# GPS.net
KiCad netlist of a schematic drawn in Altium Designer
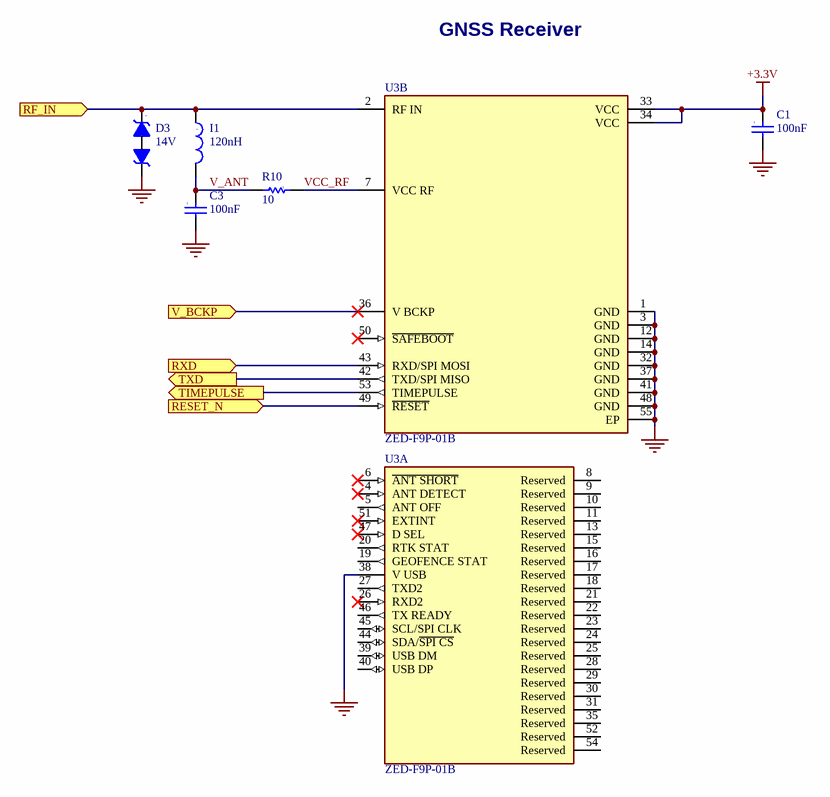
[diagram p0: GPS.SchDoc]

(export (version "E")
  (design (tool "Eeschema 10.0.6"))
  (components
    (comp (ref "C1")
      (value "100nF")
      (footprint "0402")
      (description "CAP CER .10UF 50V X7R 10% 0402")
      (fields
        (field (name "MANUFACTURER") "TDK Corporation")
        (field (name "MANUFACTURER PART NUMBER") "C1005X7R1H104K")
        (field (name "PUBLISHER") "Altium Limited")
      )
      (libsource (lib "General") (part "Cap"))
    )
    (comp (ref "C3")
      (value "100nF")
      (footprint "0402")
      (description "CAP CER .10UF 50V X7R 10% 0402")
      (fields
        (field (name "MANUFACTURER") "TDK Corporation")
        (field (name "MANUFACTURER PART NUMBER") "C1005X7R1H104K")
        (field (name "PUBLISHER") "Altium Limited")
      )
      (libsource (lib "General") (part "Cap"))
    )
    (comp (ref "D3")
      (value "Diode - Bidirectional Zener")
      (footprint "R0402")
      (description "LITTELFUSE - PESD0402-140 - DIODE, ESD PROTECTION, 0402, FULL REEL")
      (fields
        (field (name "MANUFACTURER") "Littelfuse")
        (field (name "MANUFACTURER PART NUMBER") "PESD0402-140")
        (field (name "WORKING VOLTAGE") "14V")
      )
      (libsource (lib "General") (part "Diode - Bidirectional Zener"))
    )
    (comp (ref "I1")
      (value "120nH")
      (footprint "0402")
      (description "Inductor RF Chip Wirewound 120nH 5% 100MHz 20Q-Factor 110mA 2.66Ohm DCR 0402 Paper T/R")
      (fields
        (field (name "MANUFACTURER") "Murata")
        (field (name "MANUFACTURER PART NUMBER") "LQW15ANR12J00D")
      )
      (libsource (lib "General") (part "Inductor"))
    )
    (comp (ref "R10")
      (value "10")
      (footprint "R0402")
      (description "RES SMD 10 OHM 5% 1/5W 0402")
      (fields
        (field (name "MANUFACTURER") "Rohm Semiconductor")
        (field (name "MANUFACTURER PART NUMBER") "ESR01MZPJ100")
      )
      (libsource (lib "General") (part "Res"))
    )
    (comp (ref "U3")
      (value "ZED-F9P-01B")
      (footprint "U-Blox_ZED-F9P")
      (fields (field (name "MANUFACTURER") "u-blox") (field (name "MANUFACTURER PART NUMBER") "ZED-F9P-01B"))
      (libsource (lib "Wagstaff") (part "U-Blox_ZED-F9P-01B_Client(IS)"))
    )
  )
  (nets
    (net (code "1") (name "+3.3V") (class "Default")
      (node (ref "C1") (pin "1") (pinfunction "1_1") (pintype "passive"))
      (node (ref "U3") (pin "33") (pinfunction "VCC_33") (pintype "power_in"))
      (node (ref "U3") (pin "34") (pinfunction "VCC_34") (pintype "power_in"))
    )
    (net (code "2") (name "/RESET_N") (class "Default")
      (node (ref "U3") (pin "49") (pinfunction "~{RESET}_49") (pintype "input"))
    )
    (net (code "3") (name "/RF_IN") (class "Default")
      (node (ref "D3") (pin "1") (pinfunction "1_1") (pintype "passive"))
      (node (ref "I1") (pin "1") (pinfunction "1_1") (pintype "passive"))
      (node (ref "U3") (pin "2") (pinfunction "RF_IN_2") (pintype "passive"))
    )
    (net (code "4") (name "/RXD") (class "Default")
      (node (ref "U3") (pin "43") (pinfunction "RXD/SPI_MOSI_43") (pintype "input"))
    )
    (net (code "5") (name "/TIMEPULSE") (class "Default")
      (node (ref "U3") (pin "53") (pinfunction "TIMEPULSE_53") (pintype "output"))
    )
    (net (code "6") (name "/TXD") (class "Default")
      (node (ref "U3") (pin "42") (pinfunction "TXD/SPI_MISO_42") (pintype "output"))
    )
    (net (code "7") (name "/VCC_RF") (class "Default")
      (node (ref "R10") (pin "1") (pinfunction "1_1") (pintype "passive"))
      (node (ref "U3") (pin "7") (pinfunction "VCC_RF_7") (pintype "power_in"))
    )
    (net (code "8") (name "/V_ANT") (class "Default")
      (node (ref "C3") (pin "1") (pinfunction "1_1") (pintype "passive"))
      (node (ref "I1") (pin "2") (pinfunction "2_2") (pintype "passive"))
      (node (ref "R10") (pin "2") (pinfunction "2_2") (pintype "passive"))
    )
    (net (code "9") (name "/V_BCKP") (class "Default")
      (node (ref "U3") (pin "36") (pinfunction "V_BCKP_36") (pintype "power_in+no_connect"))
    )
    (net (code "10") (name "GND") (class "Default")
      (node (ref "C1") (pin "2") (pinfunction "2_2") (pintype "passive"))
      (node (ref "C3") (pin "2") (pinfunction "2_2") (pintype "passive"))
      (node (ref "D3") (pin "2") (pinfunction "2_2") (pintype "passive"))
      (node (ref "U3") (pin "1") (pinfunction "GND_1") (pintype "power_in"))
      (node (ref "U3") (pin "12") (pinfunction "GND_12") (pintype "power_in"))
      (node (ref "U3") (pin "14") (pinfunction "GND_14") (pintype "power_in"))
      (node (ref "U3") (pin "3") (pinfunction "GND_3") (pintype "power_in"))
      (node (ref "U3") (pin "32") (pinfunction "GND_32") (pintype "power_in"))
      (node (ref "U3") (pin "37") (pinfunction "GND_37") (pintype "power_in"))
      (node (ref "U3") (pin "38") (pinfunction "V_USB_38") (pintype "power_in"))
      (node (ref "U3") (pin "41") (pinfunction "GND_41") (pintype "power_in"))
      (node (ref "U3") (pin "48") (pinfunction "GND_48") (pintype "power_in"))
      (node (ref "U3") (pin "55") (pinfunction "EP_55") (pintype "power_in"))
    )
    (net (code "11") (name "unconnected-(U3A-ANT_DETECT-Pad4)") (class "Default")
      (node (ref "U3") (pin "4") (pinfunction "ANT_DETECT_4") (pintype "input+no_connect"))
    )
    (net (code "12") (name "unconnected-(U3A-ANT_OFF-Pad5)") (class "Default")
      (node (ref "U3") (pin "5") (pinfunction "ANT_OFF_5") (pintype "output"))
    )
    (net (code "13") (name "unconnected-(U3A-D_SEL-Pad47)") (class "Default")
      (node (ref "U3") (pin "47") (pinfunction "D_SEL_47") (pintype "input+no_connect"))
    )
    (net (code "14") (name "unconnected-(U3A-EXTINT-Pad51)") (class "Default")
      (node (ref "U3") (pin "51") (pinfunction "EXTINT_51") (pintype "input+no_connect"))
    )
    (net (code "15") (name "unconnected-(U3A-GEOFENCE_STAT-Pad19)") (class "Default")
      (node (ref "U3") (pin "19") (pinfunction "GEOFENCE_STAT_19") (pintype "output"))
    )
    (net (code "16") (name "unconnected-(U3A-RTK_STAT-Pad20)") (class "Default")
      (node (ref "U3") (pin "20") (pinfunction "RTK_STAT_20") (pintype "output"))
    )
    (net (code "17") (name "unconnected-(U3A-RXD2-Pad26)") (class "Default")
      (node (ref "U3") (pin "26") (pinfunction "RXD2_26") (pintype "input+no_connect"))
    )
    (net (code "18") (name "unconnected-(U3A-Reserved-Pad8)") (class "Default")
      (node (ref "U3") (pin "8") (pinfunction "Reserved_8") (pintype "passive"))
    )
    (net (code "19") (name "unconnected-(U3A-Reserved-Pad9)") (class "Default")
      (node (ref "U3") (pin "9") (pinfunction "Reserved_9") (pintype "passive"))
    )
    (net (code "20") (name "unconnected-(U3A-Reserved-Pad10)") (class "Default")
      (node (ref "U3") (pin "10") (pinfunction "Reserved_10") (pintype "passive"))
    )
    (net (code "21") (name "unconnected-(U3A-Reserved-Pad11)") (class "Default")
      (node (ref "U3") (pin "11") (pinfunction "Reserved_11") (pintype "passive"))
    )
    (net (code "22") (name "unconnected-(U3A-Reserved-Pad13)") (class "Default")
      (node (ref "U3") (pin "13") (pinfunction "Reserved_13") (pintype "passive"))
    )
    (net (code "23") (name "unconnected-(U3A-Reserved-Pad15)") (class "Default")
      (node (ref "U3") (pin "15") (pinfunction "Reserved_15") (pintype "passive"))
    )
    (net (code "24") (name "unconnected-(U3A-Reserved-Pad16)") (class "Default")
      (node (ref "U3") (pin "16") (pinfunction "Reserved_16") (pintype "passive"))
    )
    (net (code "25") (name "unconnected-(U3A-Reserved-Pad17)") (class "Default")
      (node (ref "U3") (pin "17") (pinfunction "Reserved_17") (pintype "passive"))
    )
    (net (code "26") (name "unconnected-(U3A-Reserved-Pad18)") (class "Default")
      (node (ref "U3") (pin "18") (pinfunction "Reserved_18") (pintype "passive"))
    )
    (net (code "27") (name "unconnected-(U3A-Reserved-Pad21)") (class "Default")
      (node (ref "U3") (pin "21") (pinfunction "Reserved_21") (pintype "passive"))
    )
    (net (code "28") (name "unconnected-(U3A-Reserved-Pad22)") (class "Default")
      (node (ref "U3") (pin "22") (pinfunction "Reserved_22") (pintype "passive"))
    )
    (net (code "29") (name "unconnected-(U3A-Reserved-Pad23)") (class "Default")
      (node (ref "U3") (pin "23") (pinfunction "Reserved_23") (pintype "passive"))
    )
    (net (code "30") (name "unconnected-(U3A-Reserved-Pad24)") (class "Default")
      (node (ref "U3") (pin "24") (pinfunction "Reserved_24") (pintype "passive"))
    )
    (net (code "31") (name "unconnected-(U3A-Reserved-Pad25)") (class "Default")
      (node (ref "U3") (pin "25") (pinfunction "Reserved_25") (pintype "passive"))
    )
    (net (code "32") (name "unconnected-(U3A-Reserved-Pad28)") (class "Default")
      (node (ref "U3") (pin "28") (pinfunction "Reserved_28") (pintype "passive"))
    )
    (net (code "33") (name "unconnected-(U3A-Reserved-Pad29)") (class "Default")
      (node (ref "U3") (pin "29") (pinfunction "Reserved_29") (pintype "passive"))
    )
    (net (code "34") (name "unconnected-(U3A-Reserved-Pad30)") (class "Default")
      (node (ref "U3") (pin "30") (pinfunction "Reserved_30") (pintype "passive"))
    )
    (net (code "35") (name "unconnected-(U3A-Reserved-Pad31)") (class "Default")
      (node (ref "U3") (pin "31") (pinfunction "Reserved_31") (pintype "passive"))
    )
    (net (code "36") (name "unconnected-(U3A-Reserved-Pad35)") (class "Default")
      (node (ref "U3") (pin "35") (pinfunction "Reserved_35") (pintype "passive"))
    )
    (net (code "37") (name "unconnected-(U3A-Reserved-Pad52)") (class "Default")
      (node (ref "U3") (pin "52") (pinfunction "Reserved_52") (pintype "passive"))
    )
    (net (code "38") (name "unconnected-(U3A-Reserved-Pad54)") (class "Default")
      (node (ref "U3") (pin "54") (pinfunction "Reserved_54") (pintype "passive"))
    )
    (net (code "39") (name "unconnected-(U3A-SCL{slash}SPI_CLK-Pad45)") (class "Default")
      (node (ref "U3") (pin "45") (pinfunction "SCL/SPI_CLK_45") (pintype "bidirectional"))
    )
    (net (code "40") (name "unconnected-(U3A-SDA{slash}~{SPI_CS}-Pad44)") (class "Default")
      (node (ref "U3") (pin "44") (pinfunction "SDA/~{SPI_CS}_44") (pintype "bidirectional"))
    )
    (net (code "41") (name "unconnected-(U3A-TXD2-Pad27)") (class "Default")
      (node (ref "U3") (pin "27") (pinfunction "TXD2_27") (pintype "output"))
    )
    (net (code "42") (name "unconnected-(U3A-TX_READY-Pad46)") (class "Default")
      (node (ref "U3") (pin "46") (pinfunction "TX_READY_46") (pintype "output"))
    )
    (net (code "43") (name "unconnected-(U3A-USB_DM-Pad39)") (class "Default")
      (node (ref "U3") (pin "39") (pinfunction "USB_DM_39") (pintype "bidirectional"))
    )
    (net (code "44") (name "unconnected-(U3A-USB_DP-Pad40)") (class "Default")
      (node (ref "U3") (pin "40") (pinfunction "USB_DP_40") (pintype "bidirectional"))
    )
    (net (code "45") (name "unconnected-(U3A-~{ANT_SHORT}-Pad6)") (class "Default")
      (node (ref "U3") (pin "6") (pinfunction "~{ANT_SHORT}_6") (pintype "input+no_connect"))
    )
    (net (code "46") (name "unconnected-(U3B-~{SAFEBOOT}-Pad50)") (class "Default")
      (node (ref "U3") (pin "50") (pinfunction "~{SAFEBOOT}_50") (pintype "input+no_connect"))
    )
  )
)
